# 07-FPGA.net
KiCad netlist of a schematic drawn in Altium Designer
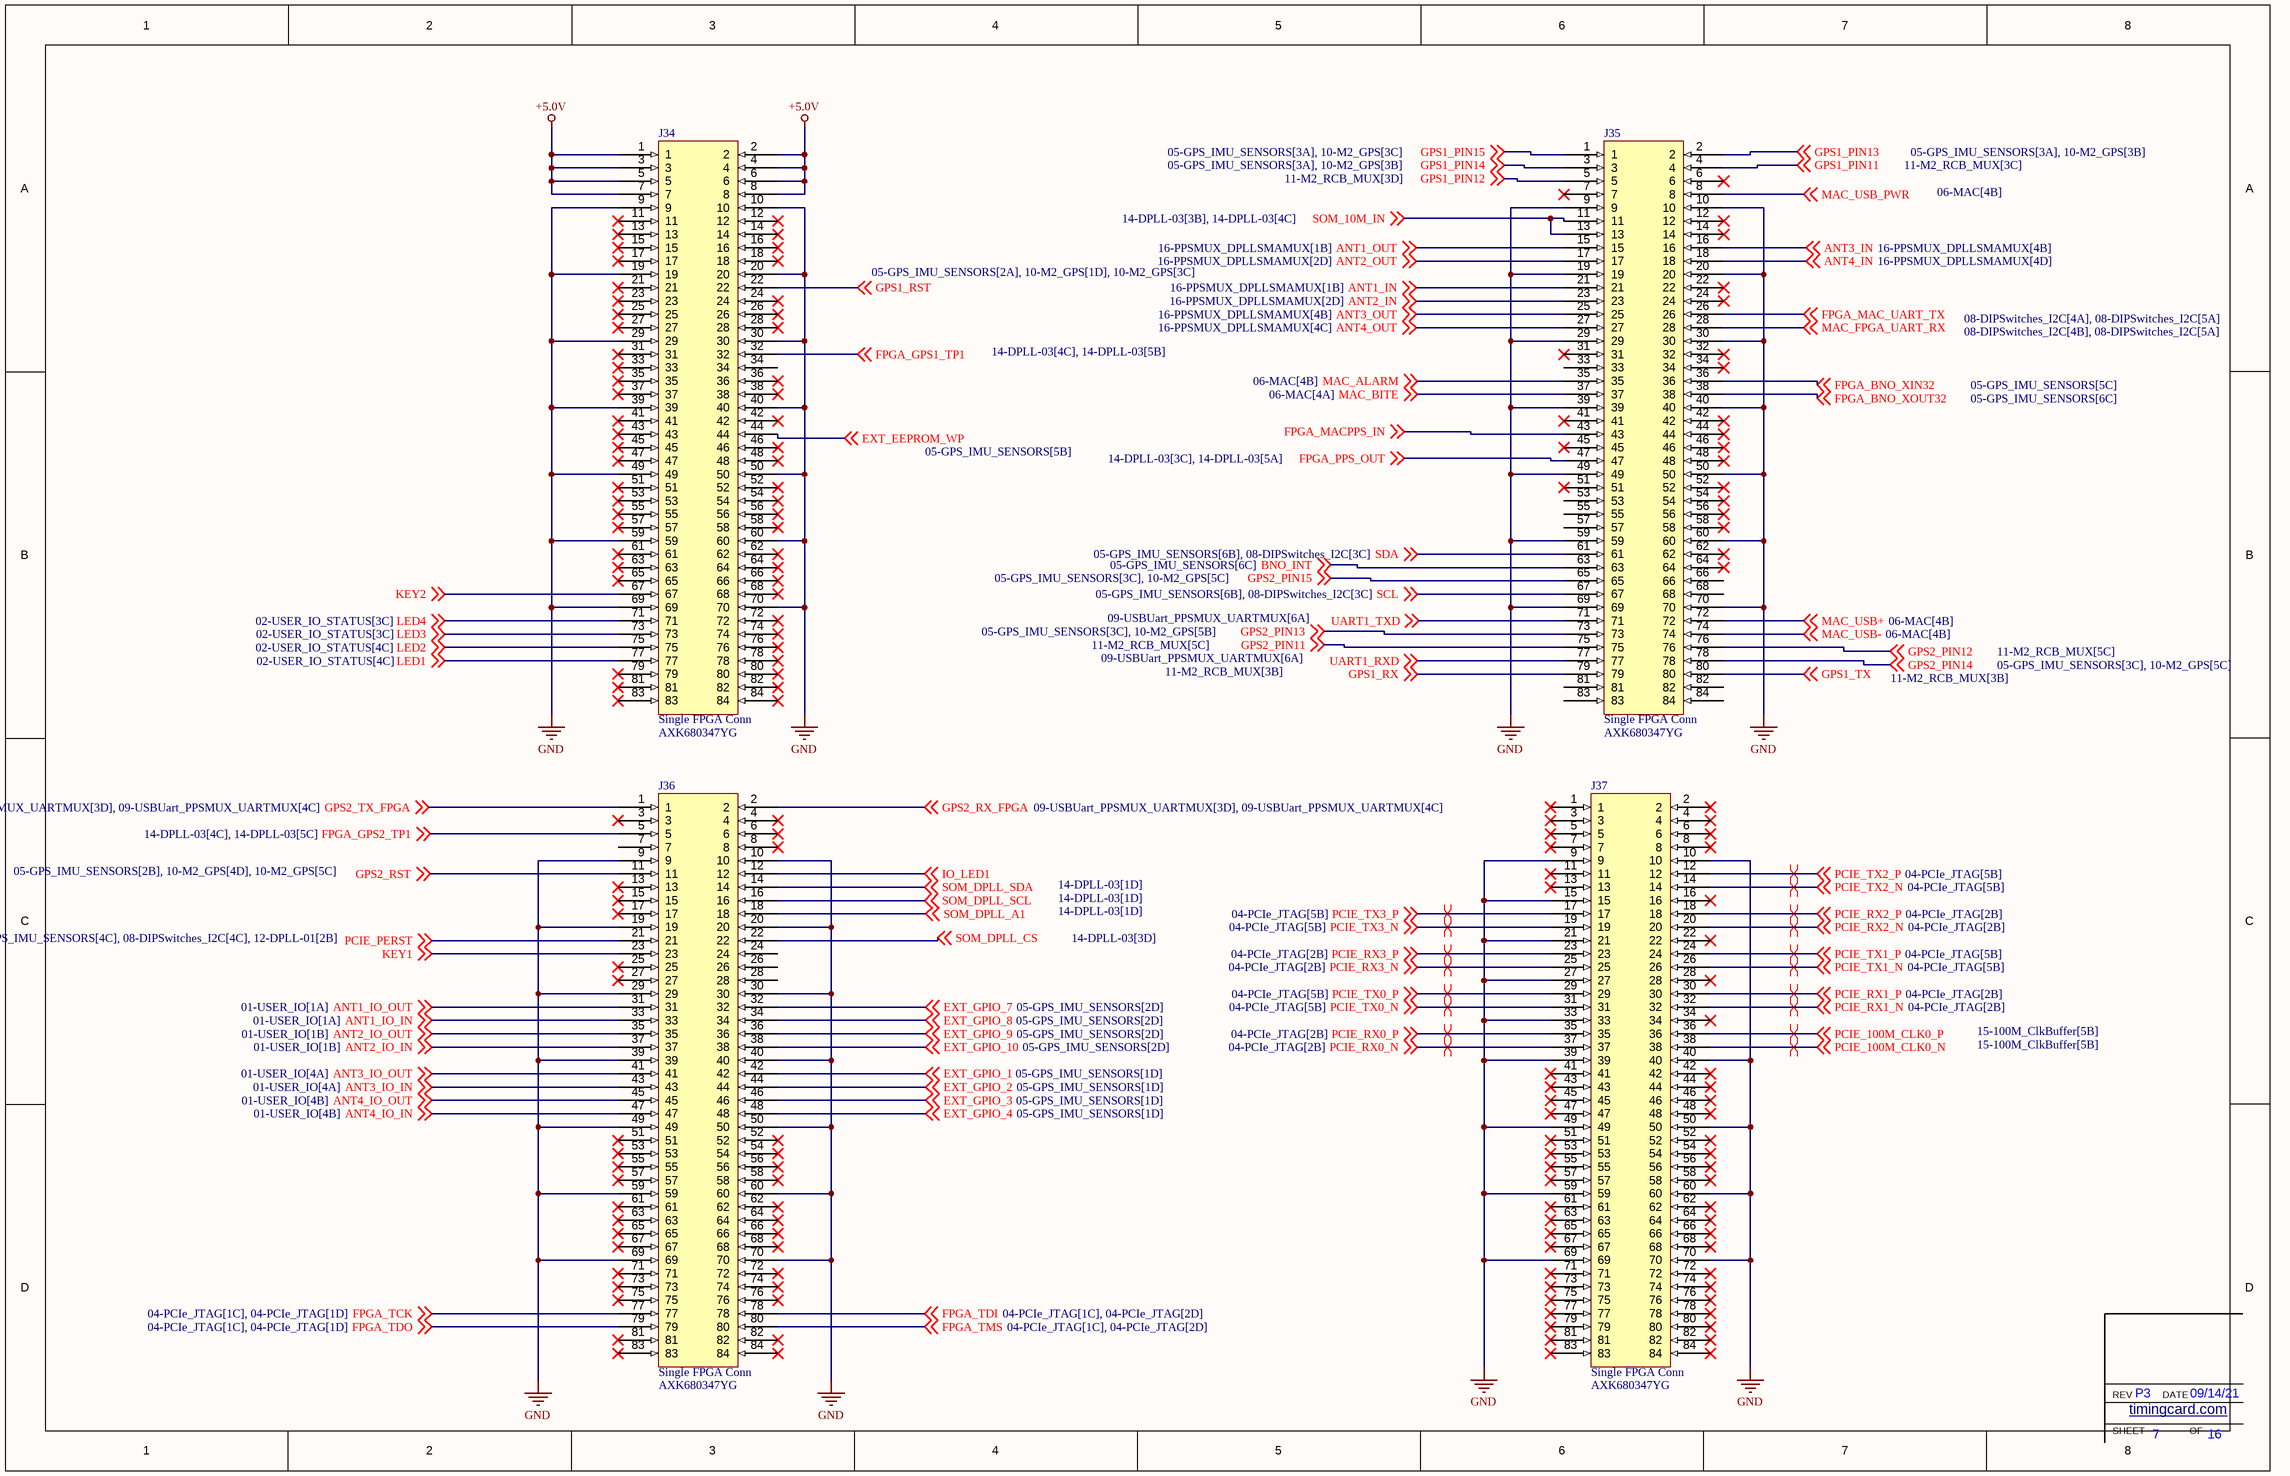
[diagram p0: 07-FPGA.SchDoc]

(export (version "E")
  (design (tool "Eeschema 10.0.6"))
  (components
    (comp (ref "J34")
      (value "Single FPGA Conn")
      (footprint "SingleFPGAConn")
      (fields (field (name "PART NUMBER") "AXK680347YG"))
      (libsource (lib "FPGA_CONN") (part "Single FPGA Conn"))
    )
    (comp (ref "J35")
      (value "Single FPGA Conn")
      (footprint "SingleFPGAConn")
      (fields (field (name "PART NUMBER") "AXK680347YG"))
      (libsource (lib "FPGA_CONN") (part "Single FPGA Conn"))
    )
    (comp (ref "J36")
      (value "Single FPGA Conn")
      (footprint "SingleFPGAConn")
      (fields (field (name "PART NUMBER") "AXK680347YG"))
      (libsource (lib "FPGA_CONN") (part "Single FPGA Conn"))
    )
    (comp (ref "J37")
      (value "Single FPGA Conn")
      (footprint "SingleFPGAConn")
      (fields (field (name "PART NUMBER") "AXK680347YG"))
      (libsource (lib "FPGA_CONN") (part "Single FPGA Conn"))
    )
  )
  (nets
    (net (code "1") (name "+5.0V") (class "Default")
      (node (ref "J34") (pin "1") (pinfunction "1_1") (pintype "input"))
      (node (ref "J34") (pin "2") (pinfunction "2_2") (pintype "input"))
      (node (ref "J34") (pin "3") (pinfunction "3_3") (pintype "input"))
      (node (ref "J34") (pin "4") (pinfunction "4_4") (pintype "input"))
      (node (ref "J34") (pin "5") (pinfunction "5_5") (pintype "input"))
      (node (ref "J34") (pin "6") (pinfunction "6_6") (pintype "input"))
      (node (ref "J34") (pin "7") (pinfunction "7_7") (pintype "input"))
      (node (ref "J34") (pin "8") (pinfunction "8_8") (pintype "input"))
    )
    (net (code "2") (name "ANT1_IN") (class "Default")
      (node (ref "J35") (pin "21") (pinfunction "21_21") (pintype "input"))
    )
    (net (code "3") (name "ANT1_IO_IN") (class "Default")
      (node (ref "J36") (pin "33") (pinfunction "33_33") (pintype "input"))
    )
    (net (code "4") (name "ANT1_IO_OUT") (class "Default")
      (node (ref "J36") (pin "31") (pinfunction "31_31") (pintype "input"))
    )
    (net (code "5") (name "ANT1_OUT") (class "Default")
      (node (ref "J35") (pin "15") (pinfunction "15_15") (pintype "input"))
    )
    (net (code "6") (name "ANT2_IN") (class "Default")
      (node (ref "J35") (pin "23") (pinfunction "23_23") (pintype "input"))
    )
    (net (code "7") (name "ANT2_IO_IN") (class "Default")
      (node (ref "J36") (pin "37") (pinfunction "37_37") (pintype "input"))
    )
    (net (code "8") (name "ANT2_IO_OUT") (class "Default")
      (node (ref "J36") (pin "35") (pinfunction "35_35") (pintype "input"))
    )
    (net (code "9") (name "ANT2_OUT") (class "Default")
      (node (ref "J35") (pin "17") (pinfunction "17_17") (pintype "input"))
    )
    (net (code "10") (name "ANT3_IN") (class "Default")
      (node (ref "J35") (pin "16") (pinfunction "16_16") (pintype "input"))
    )
    (net (code "11") (name "ANT3_IO_IN") (class "Default")
      (node (ref "J36") (pin "43") (pinfunction "43_43") (pintype "input"))
    )
    (net (code "12") (name "ANT3_IO_OUT") (class "Default")
      (node (ref "J36") (pin "41") (pinfunction "41_41") (pintype "input"))
    )
    (net (code "13") (name "ANT3_OUT") (class "Default")
      (node (ref "J35") (pin "25") (pinfunction "25_25") (pintype "input"))
    )
    (net (code "14") (name "ANT4_IN") (class "Default")
      (node (ref "J35") (pin "18") (pinfunction "18_18") (pintype "input"))
    )
    (net (code "15") (name "ANT4_IO_IN") (class "Default")
      (node (ref "J36") (pin "47") (pinfunction "47_47") (pintype "input"))
    )
    (net (code "16") (name "ANT4_IO_OUT") (class "Default")
      (node (ref "J36") (pin "45") (pinfunction "45_45") (pintype "input"))
    )
    (net (code "17") (name "ANT4_OUT") (class "Default")
      (node (ref "J35") (pin "27") (pinfunction "27_27") (pintype "input"))
    )
    (net (code "18") (name "BNO_INT") (class "Default")
      (node (ref "J35") (pin "63") (pinfunction "63_63") (pintype "input"))
    )
    (net (code "19") (name "EXT_EEPROM_WP") (class "Default")
      (node (ref "J34") (pin "44") (pinfunction "44_44") (pintype "input"))
    )
    (net (code "20") (name "EXT_GPIO_1") (class "Default")
      (node (ref "J36") (pin "42") (pinfunction "42_42") (pintype "input"))
    )
    (net (code "21") (name "EXT_GPIO_2") (class "Default")
      (node (ref "J36") (pin "44") (pinfunction "44_44") (pintype "input"))
    )
    (net (code "22") (name "EXT_GPIO_3") (class "Default")
      (node (ref "J36") (pin "46") (pinfunction "46_46") (pintype "input"))
    )
    (net (code "23") (name "EXT_GPIO_4") (class "Default")
      (node (ref "J36") (pin "48") (pinfunction "48_48") (pintype "input"))
    )
    (net (code "24") (name "EXT_GPIO_7") (class "Default")
      (node (ref "J36") (pin "32") (pinfunction "32_32") (pintype "input"))
    )
    (net (code "25") (name "EXT_GPIO_8") (class "Default")
      (node (ref "J36") (pin "34") (pinfunction "34_34") (pintype "input"))
    )
    (net (code "26") (name "EXT_GPIO_9") (class "Default")
      (node (ref "J36") (pin "36") (pinfunction "36_36") (pintype "input"))
    )
    (net (code "27") (name "EXT_GPIO_10") (class "Default")
      (node (ref "J36") (pin "38") (pinfunction "38_38") (pintype "input"))
    )
    (net (code "28") (name "FPGA_BNO_XIN32") (class "Default")
      (node (ref "J35") (pin "36") (pinfunction "36_36") (pintype "input"))
    )
    (net (code "29") (name "FPGA_BNO_XOUT32") (class "Default")
      (node (ref "J35") (pin "38") (pinfunction "38_38") (pintype "input"))
    )
    (net (code "30") (name "FPGA_GPS1_TP1") (class "Default")
      (node (ref "J34") (pin "32") (pinfunction "32_32") (pintype "input"))
    )
    (net (code "31") (name "FPGA_GPS2_TP1") (class "Default")
      (node (ref "J36") (pin "5") (pinfunction "5_5") (pintype "input"))
    )
    (net (code "32") (name "FPGA_MACPPS_IN") (class "Default")
      (node (ref "J35") (pin "43") (pinfunction "43_43") (pintype "input"))
    )
    (net (code "33") (name "FPGA_MAC_UART_TX") (class "Default")
      (node (ref "J35") (pin "26") (pinfunction "26_26") (pintype "input"))
    )
    (net (code "34") (name "FPGA_PPS_OUT") (class "Default")
      (node (ref "J35") (pin "47") (pinfunction "47_47") (pintype "input"))
    )
    (net (code "35") (name "FPGA_TCK") (class "Default")
      (node (ref "J36") (pin "77") (pinfunction "77_77") (pintype "input"))
    )
    (net (code "36") (name "FPGA_TDI") (class "Default")
      (node (ref "J36") (pin "78") (pinfunction "78_78") (pintype "input"))
    )
    (net (code "37") (name "FPGA_TDO") (class "Default")
      (node (ref "J36") (pin "79") (pinfunction "79_79") (pintype "input"))
    )
    (net (code "38") (name "FPGA_TMS") (class "Default")
      (node (ref "J36") (pin "80") (pinfunction "80_80") (pintype "input"))
    )
    (net (code "39") (name "GND") (class "Default")
      (node (ref "J34") (pin "10") (pinfunction "10_10") (pintype "input"))
      (node (ref "J34") (pin "19") (pinfunction "19_19") (pintype "input"))
      (node (ref "J34") (pin "20") (pinfunction "20_20") (pintype "input"))
      (node (ref "J34") (pin "29") (pinfunction "29_29") (pintype "input"))
      (node (ref "J34") (pin "30") (pinfunction "30_30") (pintype "input"))
      (node (ref "J34") (pin "39") (pinfunction "39_39") (pintype "input"))
      (node (ref "J34") (pin "40") (pinfunction "40_40") (pintype "input"))
      (node (ref "J34") (pin "49") (pinfunction "49_49") (pintype "input"))
      (node (ref "J34") (pin "50") (pinfunction "50_50") (pintype "input"))
      (node (ref "J34") (pin "59") (pinfunction "59_59") (pintype "input"))
      (node (ref "J34") (pin "60") (pinfunction "60_60") (pintype "input"))
      (node (ref "J34") (pin "69") (pinfunction "69_69") (pintype "input"))
      (node (ref "J34") (pin "70") (pinfunction "70_70") (pintype "input"))
      (node (ref "J34") (pin "9") (pinfunction "9_9") (pintype "input"))
      (node (ref "J35") (pin "10") (pinfunction "10_10") (pintype "input"))
      (node (ref "J35") (pin "19") (pinfunction "19_19") (pintype "input"))
      (node (ref "J35") (pin "20") (pinfunction "20_20") (pintype "input"))
      (node (ref "J35") (pin "29") (pinfunction "29_29") (pintype "input"))
      (node (ref "J35") (pin "30") (pinfunction "30_30") (pintype "input"))
      (node (ref "J35") (pin "39") (pinfunction "39_39") (pintype "input"))
      (node (ref "J35") (pin "40") (pinfunction "40_40") (pintype "input"))
      (node (ref "J35") (pin "49") (pinfunction "49_49") (pintype "input"))
      (node (ref "J35") (pin "50") (pinfunction "50_50") (pintype "input"))
      (node (ref "J35") (pin "59") (pinfunction "59_59") (pintype "input"))
      (node (ref "J35") (pin "60") (pinfunction "60_60") (pintype "input"))
      (node (ref "J35") (pin "69") (pinfunction "69_69") (pintype "input"))
      (node (ref "J35") (pin "70") (pinfunction "70_70") (pintype "input"))
      (node (ref "J35") (pin "9") (pinfunction "9_9") (pintype "input"))
      (node (ref "J36") (pin "10") (pinfunction "10_10") (pintype "input"))
      (node (ref "J36") (pin "19") (pinfunction "19_19") (pintype "input"))
      (node (ref "J36") (pin "20") (pinfunction "20_20") (pintype "input"))
      (node (ref "J36") (pin "29") (pinfunction "29_29") (pintype "input"))
      (node (ref "J36") (pin "30") (pinfunction "30_30") (pintype "input"))
      (node (ref "J36") (pin "39") (pinfunction "39_39") (pintype "input"))
      (node (ref "J36") (pin "40") (pinfunction "40_40") (pintype "input"))
      (node (ref "J36") (pin "49") (pinfunction "49_49") (pintype "input"))
      (node (ref "J36") (pin "50") (pinfunction "50_50") (pintype "input"))
      (node (ref "J36") (pin "59") (pinfunction "59_59") (pintype "input"))
      (node (ref "J36") (pin "60") (pinfunction "60_60") (pintype "input"))
      (node (ref "J36") (pin "69") (pinfunction "69_69") (pintype "input"))
      (node (ref "J36") (pin "70") (pinfunction "70_70") (pintype "input"))
      (node (ref "J36") (pin "9") (pinfunction "9_9") (pintype "input"))
      (node (ref "J37") (pin "10") (pinfunction "10_10") (pintype "input"))
      (node (ref "J37") (pin "15") (pinfunction "15_15") (pintype "input"))
      (node (ref "J37") (pin "21") (pinfunction "21_21") (pintype "input"))
      (node (ref "J37") (pin "27") (pinfunction "27_27") (pintype "input"))
      (node (ref "J37") (pin "33") (pinfunction "33_33") (pintype "input"))
      (node (ref "J37") (pin "39") (pinfunction "39_39") (pintype "input"))
      (node (ref "J37") (pin "40") (pinfunction "40_40") (pintype "input"))
      (node (ref "J37") (pin "49") (pinfunction "49_49") (pintype "input"))
      (node (ref "J37") (pin "50") (pinfunction "50_50") (pintype "input"))
      (node (ref "J37") (pin "59") (pinfunction "59_59") (pintype "input"))
      (node (ref "J37") (pin "60") (pinfunction "60_60") (pintype "input"))
      (node (ref "J37") (pin "69") (pinfunction "69_69") (pintype "input"))
      (node (ref "J37") (pin "70") (pinfunction "70_70") (pintype "input"))
      (node (ref "J37") (pin "9") (pinfunction "9_9") (pintype "input"))
    )
    (net (code "40") (name "GPS1_PIN11") (class "Default")
      (node (ref "J35") (pin "4") (pinfunction "4_4") (pintype "input"))
    )
    (net (code "41") (name "GPS1_PIN12") (class "Default")
      (node (ref "J35") (pin "5") (pinfunction "5_5") (pintype "input"))
    )
    (net (code "42") (name "GPS1_PIN13") (class "Default")
      (node (ref "J35") (pin "2") (pinfunction "2_2") (pintype "input"))
    )
    (net (code "43") (name "GPS1_PIN14") (class "Default")
      (node (ref "J35") (pin "3") (pinfunction "3_3") (pintype "input"))
    )
    (net (code "44") (name "GPS1_PIN15") (class "Default")
      (node (ref "J35") (pin "1") (pinfunction "1_1") (pintype "input"))
    )
    (net (code "45") (name "GPS1_RST") (class "Default")
      (node (ref "J34") (pin "22") (pinfunction "22_22") (pintype "input"))
    )
    (net (code "46") (name "GPS1_RX") (class "Default")
      (node (ref "J35") (pin "79") (pinfunction "79_79") (pintype "input"))
    )
    (net (code "47") (name "GPS1_TX") (class "Default")
      (node (ref "J35") (pin "80") (pinfunction "80_80") (pintype "input"))
    )
    (net (code "48") (name "GPS2_PIN11") (class "Default")
      (node (ref "J35") (pin "75") (pinfunction "75_75") (pintype "input"))
    )
    (net (code "49") (name "GPS2_PIN12") (class "Default")
      (node (ref "J35") (pin "76") (pinfunction "76_76") (pintype "input"))
    )
    (net (code "50") (name "GPS2_PIN13") (class "Default")
      (node (ref "J35") (pin "73") (pinfunction "73_73") (pintype "input"))
    )
    (net (code "51") (name "GPS2_PIN14") (class "Default")
      (node (ref "J35") (pin "78") (pinfunction "78_78") (pintype "input"))
    )
    (net (code "52") (name "GPS2_PIN15") (class "Default")
      (node (ref "J35") (pin "65") (pinfunction "65_65") (pintype "input"))
    )
    (net (code "53") (name "GPS2_RST") (class "Default")
      (node (ref "J36") (pin "11") (pinfunction "11_11") (pintype "input"))
    )
    (net (code "54") (name "GPS2_RX_FPGA") (class "Default")
      (node (ref "J36") (pin "2") (pinfunction "2_2") (pintype "input"))
    )
    (net (code "55") (name "GPS2_TX_FPGA") (class "Default")
      (node (ref "J36") (pin "1") (pinfunction "1_1") (pintype "input"))
    )
    (net (code "56") (name "IO_LED1") (class "Default")
      (node (ref "J36") (pin "12") (pinfunction "12_12") (pintype "input"))
    )
    (net (code "57") (name "KEY1") (class "Default")
      (node (ref "J36") (pin "23") (pinfunction "23_23") (pintype "input"))
    )
    (net (code "58") (name "KEY2") (class "Default")
      (node (ref "J34") (pin "67") (pinfunction "67_67") (pintype "input"))
    )
    (net (code "59") (name "LED1") (class "Default")
      (node (ref "J34") (pin "77") (pinfunction "77_77") (pintype "input"))
    )
    (net (code "60") (name "LED2") (class "Default")
      (node (ref "J34") (pin "75") (pinfunction "75_75") (pintype "input"))
    )
    (net (code "61") (name "LED3") (class "Default")
      (node (ref "J34") (pin "73") (pinfunction "73_73") (pintype "input"))
    )
    (net (code "62") (name "LED4") (class "Default")
      (node (ref "J34") (pin "71") (pinfunction "71_71") (pintype "input"))
    )
    (net (code "63") (name "MAC_ALARM") (class "Default")
      (node (ref "J35") (pin "35") (pinfunction "35_35") (pintype "input"))
    )
    (net (code "64") (name "MAC_BITE") (class "Default")
      (node (ref "J35") (pin "37") (pinfunction "37_37") (pintype "input"))
    )
    (net (code "65") (name "MAC_FPGA_UART_RX") (class "Default")
      (node (ref "J35") (pin "28") (pinfunction "28_28") (pintype "input"))
    )
    (net (code "66") (name "MAC_USB+") (class "Default")
      (node (ref "J35") (pin "72") (pinfunction "72_72") (pintype "input"))
    )
    (net (code "67") (name "MAC_USB-") (class "Default")
      (node (ref "J35") (pin "74") (pinfunction "74_74") (pintype "input"))
    )
    (net (code "68") (name "MAC_USB_PWR") (class "Default")
      (node (ref "J35") (pin "8") (pinfunction "8_8") (pintype "input"))
    )
    (net (code "69") (name "PCIE_100M_CLK0_N") (class "Default")
      (node (ref "J37") (pin "38") (pinfunction "38_38") (pintype "input"))
    )
    (net (code "70") (name "PCIE_100M_CLK0_P") (class "Default")
      (node (ref "J37") (pin "36") (pinfunction "36_36") (pintype "input"))
    )
    (net (code "71") (name "PCIE_PERST") (class "Default")
      (node (ref "J36") (pin "21") (pinfunction "21_21") (pintype "input"))
    )
    (net (code "72") (name "PCIE_RX0_N") (class "Default")
      (node (ref "J37") (pin "37") (pinfunction "37_37") (pintype "input"))
    )
    (net (code "73") (name "PCIE_RX0_P") (class "Default")
      (node (ref "J37") (pin "35") (pinfunction "35_35") (pintype "input"))
    )
    (net (code "74") (name "PCIE_RX1_N") (class "Default")
      (node (ref "J37") (pin "32") (pinfunction "32_32") (pintype "input"))
    )
    (net (code "75") (name "PCIE_RX1_P") (class "Default")
      (node (ref "J37") (pin "30") (pinfunction "30_30") (pintype "input"))
    )
    (net (code "76") (name "PCIE_RX2_N") (class "Default")
      (node (ref "J37") (pin "20") (pinfunction "20_20") (pintype "input"))
    )
    (net (code "77") (name "PCIE_RX2_P") (class "Default")
      (node (ref "J37") (pin "18") (pinfunction "18_18") (pintype "input"))
    )
    (net (code "78") (name "PCIE_RX3_N") (class "Default")
      (node (ref "J37") (pin "25") (pinfunction "25_25") (pintype "input"))
    )
    (net (code "79") (name "PCIE_RX3_P") (class "Default")
      (node (ref "J37") (pin "23") (pinfunction "23_23") (pintype "input"))
    )
    (net (code "80") (name "PCIE_TX0_N") (class "Default")
      (node (ref "J37") (pin "31") (pinfunction "31_31") (pintype "input"))
    )
    (net (code "81") (name "PCIE_TX0_P") (class "Default")
      (node (ref "J37") (pin "29") (pinfunction "29_29") (pintype "input"))
    )
    (net (code "82") (name "PCIE_TX1_N") (class "Default")
      (node (ref "J37") (pin "26") (pinfunction "26_26") (pintype "input"))
    )
    (net (code "83") (name "PCIE_TX1_P") (class "Default")
      (node (ref "J37") (pin "24") (pinfunction "24_24") (pintype "input"))
    )
    (net (code "84") (name "PCIE_TX2_N") (class "Default")
      (node (ref "J37") (pin "14") (pinfunction "14_14") (pintype "input"))
    )
    (net (code "85") (name "PCIE_TX2_P") (class "Default")
      (node (ref "J37") (pin "12") (pinfunction "12_12") (pintype "input"))
    )
    (net (code "86") (name "PCIE_TX3_N") (class "Default")
      (node (ref "J37") (pin "19") (pinfunction "19_19") (pintype "input"))
    )
    (net (code "87") (name "PCIE_TX3_P") (class "Default")
      (node (ref "J37") (pin "17") (pinfunction "17_17") (pintype "input"))
    )
    (net (code "88") (name "SCL") (class "Default")
      (node (ref "J35") (pin "67") (pinfunction "67_67") (pintype "input"))
    )
    (net (code "89") (name "SDA") (class "Default")
      (node (ref "J35") (pin "61") (pinfunction "61_61") (pintype "input"))
    )
    (net (code "90") (name "SOM_10M_IN") (class "Default")
      (node (ref "J35") (pin "11") (pinfunction "11_11") (pintype "input"))
      (node (ref "J35") (pin "13") (pinfunction "13_13") (pintype "input"))
    )
    (net (code "91") (name "SOM_DPLL_A1") (class "Default")
      (node (ref "J36") (pin "18") (pinfunction "18_18") (pintype "input"))
    )
    (net (code "92") (name "SOM_DPLL_CS") (class "Default")
      (node (ref "J36") (pin "22") (pinfunction "22_22") (pintype "input"))
    )
    (net (code "93") (name "SOM_DPLL_SCL") (class "Default")
      (node (ref "J36") (pin "16") (pinfunction "16_16") (pintype "input"))
    )
    (net (code "94") (name "SOM_DPLL_SDA") (class "Default")
      (node (ref "J36") (pin "14") (pinfunction "14_14") (pintype "input"))
    )
    (net (code "95") (name "UART1_RXD") (class "Default")
      (node (ref "J35") (pin "77") (pinfunction "77_77") (pintype "input"))
    )
    (net (code "96") (name "UART1_TXD") (class "Default")
      (node (ref "J35") (pin "71") (pinfunction "71_71") (pintype "input"))
    )
    (net (code "97") (name "unconnected-(J34-Pad11)") (class "Default")
      (node (ref "J34") (pin "11") (pinfunction "11_11") (pintype "input+no_connect"))
    )
    (net (code "98") (name "unconnected-(J34-Pad12)") (class "Default")
      (node (ref "J34") (pin "12") (pinfunction "12_12") (pintype "input+no_connect"))
    )
    (net (code "99") (name "unconnected-(J34-Pad13)") (class "Default")
      (node (ref "J34") (pin "13") (pinfunction "13_13") (pintype "input+no_connect"))
    )
    (net (code "100") (name "unconnected-(J34-Pad14)") (class "Default")
      (node (ref "J34") (pin "14") (pinfunction "14_14") (pintype "input+no_connect"))
    )
    (net (code "101") (name "unconnected-(J34-Pad15)") (class "Default")
      (node (ref "J34") (pin "15") (pinfunction "15_15") (pintype "input+no_connect"))
    )
    (net (code "102") (name "unconnected-(J34-Pad16)") (class "Default")
      (node (ref "J34") (pin "16") (pinfunction "16_16") (pintype "input+no_connect"))
    )
    (net (code "103") (name "unconnected-(J34-Pad17)") (class "Default")
      (node (ref "J34") (pin "17") (pinfunction "17_17") (pintype "input+no_connect"))
    )
    (net (code "104") (name "unconnected-(J34-Pad18)") (class "Default")
      (node (ref "J34") (pin "18") (pinfunction "18_18") (pintype "input+no_connect"))
    )
    (net (code "105") (name "unconnected-(J34-Pad21)") (class "Default")
      (node (ref "J34") (pin "21") (pinfunction "21_21") (pintype "input+no_connect"))
    )
    (net (code "106") (name "unconnected-(J34-Pad23)") (class "Default")
      (node (ref "J34") (pin "23") (pinfunction "23_23") (pintype "input+no_connect"))
    )
    (net (code "107") (name "unconnected-(J34-Pad24)") (class "Default")
      (node (ref "J34") (pin "24") (pinfunction "24_24") (pintype "input+no_connect"))
    )
    (net (code "108") (name "unconnected-(J34-Pad25)") (class "Default")
      (node (ref "J34") (pin "25") (pinfunction "25_25") (pintype "input+no_connect"))
    )
    (net (code "109") (name "unconnected-(J34-Pad26)") (class "Default")
      (node (ref "J34") (pin "26") (pinfunction "26_26") (pintype "input+no_connect"))
    )
    (net (code "110") (name "unconnected-(J34-Pad27)") (class "Default")
      (node (ref "J34") (pin "27") (pinfunction "27_27") (pintype "input+no_connect"))
    )
    (net (code "111") (name "unconnected-(J34-Pad28)") (class "Default")
      (node (ref "J34") (pin "28") (pinfunction "28_28") (pintype "input+no_connect"))
    )
    (net (code "112") (name "unconnected-(J34-Pad31)") (class "Default")
      (node (ref "J34") (pin "31") (pinfunction "31_31") (pintype "input+no_connect"))
    )
    (net (code "113") (name "unconnected-(J34-Pad33)") (class "Default")
      (node (ref "J34") (pin "33") (pinfunction "33_33") (pintype "input+no_connect"))
    )
    (net (code "114") (name "unconnected-(J34-Pad34)") (class "Default")
      (node (ref "J34") (pin "34") (pinfunction "34_34") (pintype "input"))
    )
    (net (code "115") (name "unconnected-(J34-Pad35)") (class "Default")
      (node (ref "J34") (pin "35") (pinfunction "35_35") (pintype "input+no_connect"))
    )
    (net (code "116") (name "unconnected-(J34-Pad36)") (class "Default")
      (node (ref "J34") (pin "36") (pinfunction "36_36") (pintype "input+no_connect"))
    )
    (net (code "117") (name "unconnected-(J34-Pad37)") (class "Default")
      (node (ref "J34") (pin "37") (pinfunction "37_37") (pintype "input+no_connect"))
    )
    (net (code "118") (name "unconnected-(J34-Pad38)") (class "Default")
      (node (ref "J34") (pin "38") (pinfunction "38_38") (pintype "input+no_connect"))
    )
    (net (code "119") (name "unconnected-(J34-Pad41)") (class "Default")
      (node (ref "J34") (pin "41") (pinfunction "41_41") (pintype "input+no_connect"))
    )
    (net (code "120") (name "unconnected-(J34-Pad42)") (class "Default")
      (node (ref "J34") (pin "42") (pinfunction "42_42") (pintype "input+no_connect"))
    )
    (net (code "121") (name "unconnected-(J34-Pad43)") (class "Default")
      (node (ref "J34") (pin "43") (pinfunction "43_43") (pintype "input+no_connect"))
    )
    (net (code "122") (name "unconnected-(J34-Pad45)") (class "Default")
      (node (ref "J34") (pin "45") (pinfunction "45_45") (pintype "input+no_connect"))
    )
    (net (code "123") (name "unconnected-(J34-Pad46)") (class "Default")
      (node (ref "J34") (pin "46") (pinfunction "46_46") (pintype "input+no_connect"))
    )
    (net (code "124") (name "unconnected-(J34-Pad47)") (class "Default")
      (node (ref "J34") (pin "47") (pinfunction "47_47") (pintype "input+no_connect"))
    )
    (net (code "125") (name "unconnected-(J34-Pad48)") (class "Default")
      (node (ref "J34") (pin "48") (pinfunction "48_48") (pintype "input+no_connect"))
    )
    (net (code "126") (name "unconnected-(J34-Pad51)") (class "Default")
      (node (ref "J34") (pin "51") (pinfunction "51_51") (pintype "input+no_connect"))
    )
    (net (code "127") (name "unconnected-(J34-Pad52)") (class "Default")
      (node (ref "J34") (pin "52") (pinfunction "52_52") (pintype "input+no_connect"))
    )
    (net (code "128") (name "unconnected-(J34-Pad53)") (class "Default")
      (node (ref "J34") (pin "53") (pinfunction "53_53") (pintype "input+no_connect"))
    )
    (net (code "129") (name "unconnected-(J34-Pad54)") (class "Default")
      (node (ref "J34") (pin "54") (pinfunction "54_54") (pintype "input+no_connect"))
    )
    (net (code "130") (name "unconnected-(J34-Pad55)") (class "Default")
      (node (ref "J34") (pin "55") (pinfunction "55_55") (pintype "input+no_connect"))
    )
    (net (code "131") (name "unconnected-(J34-Pad56)") (class "Default")
      (node (ref "J34") (pin "56") (pinfunction "56_56") (pintype "input+no_connect"))
    )
    (net (code "132") (name "unconnected-(J34-Pad57)") (class "Default")
      (node (ref "J34") (pin "57") (pinfunction "57_57") (pintype "input+no_connect"))
    )
    (net (code "133") (name "unconnected-(J34-Pad58)") (class "Default")
      (node (ref "J34") (pin "58") (pinfunction "58_58") (pintype "input+no_connect"))
    )
    (net (code "134") (name "unconnected-(J34-Pad61)") (class "Default")
      (node (ref "J34") (pin "61") (pinfunction "61_61") (pintype "input+no_connect"))
    )
    (net (code "135") (name "unconnected-(J34-Pad62)") (class "Default")
      (node (ref "J34") (pin "62") (pinfunction "62_62") (pintype "input+no_connect"))
    )
    (net (code "136") (name "unconnected-(J34-Pad63)") (class "Default")
      (node (ref "J34") (pin "63") (pinfunction "63_63") (pintype "input+no_connect"))
    )
    (net (code "137") (name "unconnected-(J34-Pad64)") (class "Default")
      (node (ref "J34") (pin "64") (pinfunction "64_64") (pintype "input+no_connect"))
    )
    (net (code "138") (name "unconnected-(J34-Pad65)") (class "Default")
      (node (ref "J34") (pin "65") (pinfunction "65_65") (pintype "input+no_connect"))
    )
    (net (code "139") (name "unconnected-(J34-Pad66)") (class "Default")
      (node (ref "J34") (pin "66") (pinfunction "66_66") (pintype "input+no_connect"))
    )
    (net (code "140") (name "unconnected-(J34-Pad68)") (class "Default")
      (node (ref "J34") (pin "68") (pinfunction "68_68") (pintype "input+no_connect"))
    )
    (net (code "141") (name "unconnected-(J34-Pad72)") (class "Default")
      (node (ref "J34") (pin "72") (pinfunction "72_72") (pintype "input+no_connect"))
    )
    (net (code "142") (name "unconnected-(J34-Pad74)") (class "Default")
      (node (ref "J34") (pin "74") (pinfunction "74_74") (pintype "input+no_connect"))
    )
    (net (code "143") (name "unconnected-(J34-Pad76)") (class "Default")
      (node (ref "J34") (pin "76") (pinfunction "76_76") (pintype "input+no_connect"))
    )
    (net (code "144") (name "unconnected-(J34-Pad78)") (class "Default")
      (node (ref "J34") (pin "78") (pinfunction "78_78") (pintype "input+no_connect"))
    )
    (net (code "145") (name "unconnected-(J34-Pad79)") (class "Default")
      (node (ref "J34") (pin "79") (pinfunction "79_79") (pintype "input+no_connect"))
    )
    (net (code "146") (name "unconnected-(J34-Pad80)") (class "Default")
      (node (ref "J34") (pin "80") (pinfunction "80_80") (pintype "input+no_connect"))
    )
    (net (code "147") (name "unconnected-(J34-Pad81)") (class "Default")
      (node (ref "J34") (pin "81") (pinfunction "81_81") (pintype "input+no_connect"))
    )
    (net (code "148") (name "unconnected-(J34-Pad82)") (class "Default")
      (node (ref "J34") (pin "82") (pinfunction "82_82") (pintype "input+no_connect"))
    )
    (net (code "149") (name "unconnected-(J34-Pad83)") (class "Default")
      (node (ref "J34") (pin "83") (pinfunction "83_83") (pintype "input+no_connect"))
    )
    (net (code "150") (name "unconnected-(J34-Pad84)") (class "Default")
      (node (ref "J34") (pin "84") (pinfunction "84_84") (pintype "input+no_connect"))
    )
    (net (code "151") (name "unconnected-(J35-Pad6)") (class "Default")
      (node (ref "J35") (pin "6") (pinfunction "6_6") (pintype "input+no_connect"))
    )
    (net (code "152") (name "unconnected-(J35-Pad7)") (class "Default")
      (node (ref "J35") (pin "7") (pinfunction "7_7") (pintype "input+no_connect"))
    )
    (net (code "153") (name "unconnected-(J35-Pad12)") (class "Default")
      (node (ref "J35") (pin "12") (pinfunction "12_12") (pintype "input+no_connect"))
    )
    (net (code "154") (name "unconnected-(J35-Pad14)") (class "Default")
      (node (ref "J35") (pin "14") (pinfunction "14_14") (pintype "input+no_connect"))
    )
    (net (code "155") (name "unconnected-(J35-Pad22)") (class "Default")
      (node (ref "J35") (pin "22") (pinfunction "22_22") (pintype "input+no_connect"))
    )
    (net (code "156") (name "unconnected-(J35-Pad24)") (class "Default")
      (node (ref "J35") (pin "24") (pinfunction "24_24") (pintype "input+no_connect"))
    )
    (net (code "157") (name "unconnected-(J35-Pad31)") (class "Default")
      (node (ref "J35") (pin "31") (pinfunction "31_31") (pintype "input+no_connect"))
    )
    (net (code "158") (name "unconnected-(J35-Pad32)") (class "Default")
      (node (ref "J35") (pin "32") (pinfunction "32_32") (pintype "input+no_connect"))
    )
    (net (code "159") (name "unconnected-(J35-Pad33)") (class "Default")
      (node (ref "J35") (pin "33") (pinfunction "33_33") (pintype "input"))
    )
    (net (code "160") (name "unconnected-(J35-Pad34)") (class "Default")
      (node (ref "J35") (pin "34") (pinfunction "34_34") (pintype "input+no_connect"))
    )
    (net (code "161") (name "unconnected-(J35-Pad41)") (class "Default")
      (node (ref "J35") (pin "41") (pinfunction "41_41") (pintype "input+no_connect"))
    )
    (net (code "162") (name "unconnected-(J35-Pad42)") (class "Default")
      (node (ref "J35") (pin "42") (pinfunction "42_42") (pintype "input+no_connect"))
    )
    (net (code "163") (name "unconnected-(J35-Pad44)") (class "Default")
      (node (ref "J35") (pin "44") (pinfunction "44_44") (pintype "input+no_connect"))
    )
    (net (code "164") (name "unconnected-(J35-Pad45)") (class "Default")
      (node (ref "J35") (pin "45") (pinfunction "45_45") (pintype "input+no_connect"))
    )
    (net (code "165") (name "unconnected-(J35-Pad46)") (class "Default")
      (node (ref "J35") (pin "46") (pinfunction "46_46") (pintype "input+no_connect"))
    )
    (net (code "166") (name "unconnected-(J35-Pad48)") (class "Default")
      (node (ref "J35") (pin "48") (pinfunction "48_48") (pintype "input+no_connect"))
    )
    (net (code "167") (name "unconnected-(J35-Pad51)") (class "Default")
      (node (ref "J35") (pin "51") (pinfunction "51_51") (pintype "input+no_connect"))
    )
    (net (code "168") (name "unconnected-(J35-Pad52)") (class "Default")
      (node (ref "J35") (pin "52") (pinfunction "52_52") (pintype "input+no_connect"))
    )
    (net (code "169") (name "unconnected-(J35-Pad53)") (class "Default")
      (node (ref "J35") (pin "53") (pinfunction "53_53") (pintype "input"))
    )
    (net (code "170") (name "unconnected-(J35-Pad54)") (class "Default")
      (node (ref "J35") (pin "54") (pinfunction "54_54") (pintype "input+no_connect"))
    )
    (net (code "171") (name "unconnected-(J35-Pad55)") (class "Default")
      (node (ref "J35") (pin "55") (pinfunction "55_55") (pintype "input"))
    )
    (net (code "172") (name "unconnected-(J35-Pad56)") (class "Default")
      (node (ref "J35") (pin "56") (pinfunction "56_56") (pintype "input+no_connect"))
    )
    (net (code "173") (name "unconnected-(J35-Pad57)") (class "Default")
      (node (ref "J35") (pin "57") (pinfunction "57_57") (pintype "input"))
    )
    (net (code "174") (name "unconnected-(J35-Pad58)") (class "Default")
      (node (ref "J35") (pin "58") (pinfunction "58_58") (pintype "input+no_connect"))
    )
    (net (code "175") (name "unconnected-(J35-Pad62)") (class "Default")
      (node (ref "J35") (pin "62") (pinfunction "62_62") (pintype "input+no_connect"))
    )
    (net (code "176") (name "unconnected-(J35-Pad64)") (class "Default")
      (node (ref "J35") (pin "64") (pinfunction "64_64") (pintype "input+no_connect"))
    )
    (net (code "177") (name "unconnected-(J35-Pad66)") (class "Default")
      (node (ref "J35") (pin "66") (pinfunction "66_66") (pintype "input"))
    )
    (net (code "178") (name "unconnected-(J35-Pad68)") (class "Default")
      (node (ref "J35") (pin "68") (pinfunction "68_68") (pintype "input"))
    )
    (net (code "179") (name "unconnected-(J35-Pad81)") (class "Default")
      (node (ref "J35") (pin "81") (pinfunction "81_81") (pintype "input"))
    )
    (net (code "180") (name "unconnected-(J35-Pad82)") (class "Default")
      (node (ref "J35") (pin "82") (pinfunction "82_82") (pintype "input"))
    )
    (net (code "181") (name "unconnected-(J35-Pad83)") (class "Default")
      (node (ref "J35") (pin "83") (pinfunction "83_83") (pintype "input"))
    )
    (net (code "182") (name "unconnected-(J35-Pad84)") (class "Default")
      (node (ref "J35") (pin "84") (pinfunction "84_84") (pintype "input"))
    )
    (net (code "183") (name "unconnected-(J36-Pad3)") (class "Default")
      (node (ref "J36") (pin "3") (pinfunction "3_3") (pintype "input+no_connect"))
    )
    (net (code "184") (name "unconnected-(J36-Pad4)") (class "Default")
      (node (ref "J36") (pin "4") (pinfunction "4_4") (pintype "input+no_connect"))
    )
    (net (code "185") (name "unconnected-(J36-Pad6)") (class "Default")
      (node (ref "J36") (pin "6") (pinfunction "6_6") (pintype "input+no_connect"))
    )
    (net (code "186") (name "unconnected-(J36-Pad7)") (class "Default")
      (node (ref "J36") (pin "7") (pinfunction "7_7") (pintype "input"))
    )
    (net (code "187") (name "unconnected-(J36-Pad8)") (class "Default")
      (node (ref "J36") (pin "8") (pinfunction "8_8") (pintype "input+no_connect"))
    )
    (net (code "188") (name "unconnected-(J36-Pad13)") (class "Default")
      (node (ref "J36") (pin "13") (pinfunction "13_13") (pintype "input+no_connect"))
    )
    (net (code "189") (name "unconnected-(J36-Pad15)") (class "Default")
      (node (ref "J36") (pin "15") (pinfunction "15_15") (pintype "input+no_connect"))
    )
    (net (code "190") (name "unconnected-(J36-Pad17)") (class "Default")
      (node (ref "J36") (pin "17") (pinfunction "17_17") (pintype "input+no_connect"))
    )
    (net (code "191") (name "unconnected-(J36-Pad24)") (class "Default")
      (node (ref "J36") (pin "24") (pinfunction "24_24") (pintype "input"))
    )
    (net (code "192") (name "unconnected-(J36-Pad25)") (class "Default")
      (node (ref "J36") (pin "25") (pinfunction "25_25") (pintype "input+no_connect"))
    )
    (net (code "193") (name "unconnected-(J36-Pad26)") (class "Default")
      (node (ref "J36") (pin "26") (pinfunction "26_26") (pintype "input"))
    )
    (net (code "194") (name "unconnected-(J36-Pad27)") (class "Default")
      (node (ref "J36") (pin "27") (pinfunction "27_27") (pintype "input+no_connect"))
    )
    (net (code "195") (name "unconnected-(J36-Pad28)") (class "Default")
      (node (ref "J36") (pin "28") (pinfunction "28_28") (pintype "input"))
    )
    (net (code "196") (name "unconnected-(J36-Pad51)") (class "Default")
      (node (ref "J36") (pin "51") (pinfunction "51_51") (pintype "input+no_connect"))
    )
    (net (code "197") (name "unconnected-(J36-Pad52)") (class "Default")
      (node (ref "J36") (pin "52") (pinfunction "52_52") (pintype "input+no_connect"))
    )
    (net (code "198") (name "unconnected-(J36-Pad53)") (class "Default")
      (node (ref "J36") (pin "53") (pinfunction "53_53") (pintype "input+no_connect"))
    )
    (net (code "199") (name "unconnected-(J36-Pad54)") (class "Default")
      (node (ref "J36") (pin "54") (pinfunction "54_54") (pintype "input+no_connect"))
    )
    (net (code "200") (name "unconnected-(J36-Pad55)") (class "Default")
      (node (ref "J36") (pin "55") (pinfunction "55_55") (pintype "input+no_connect"))
    )
    (net (code "201") (name "unconnected-(J36-Pad56)") (class "Default")
      (node (ref "J36") (pin "56") (pinfunction "56_56") (pintype "input+no_connect"))
    )
    (net (code "202") (name "unconnected-(J36-Pad57)") (class "Default")
      (node (ref "J36") (pin "57") (pinfunction "57_57") (pintype "input+no_connect"))
    )
    (net (code "203") (name "unconnected-(J36-Pad58)") (class "Default")
      (node (ref "J36") (pin "58") (pinfunction "58_58") (pintype "input+no_connect"))
    )
    (net (code "204") (name "unconnected-(J36-Pad61)") (class "Default")
      (node (ref "J36") (pin "61") (pinfunction "61_61") (pintype "input+no_connect"))
    )
    (net (code "205") (name "unconnected-(J36-Pad62)") (class "Default")
      (node (ref "J36") (pin "62") (pinfunction "62_62") (pintype "input+no_connect"))
    )
    (net (code "206") (name "unconnected-(J36-Pad63)") (class "Default")
      (node (ref "J36") (pin "63") (pinfunction "63_63") (pintype "input+no_connect"))
    )
    (net (code "207") (name "unconnected-(J36-Pad64)") (class "Default")
      (node (ref "J36") (pin "64") (pinfunction "64_64") (pintype "input+no_connect"))
    )
    (net (code "208") (name "unconnected-(J36-Pad65)") (class "Default")
      (node (ref "J36") (pin "65") (pinfunction "65_65") (pintype "input+no_connect"))
    )
    (net (code "209") (name "unconnected-(J36-Pad66)") (class "Default")
      (node (ref "J36") (pin "66") (pinfunction "66_66") (pintype "input+no_connect"))
    )
    (net (code "210") (name "unconnected-(J36-Pad67)") (class "Default")
      (node (ref "J36") (pin "67") (pinfunction "67_67") (pintype "input+no_connect"))
    )
    (net (code "211") (name "unconnected-(J36-Pad68)") (class "Default")
      (node (ref "J36") (pin "68") (pinfunction "68_68") (pintype "input+no_connect"))
    )
    (net (code "212") (name "unconnected-(J36-Pad71)") (class "Default")
      (node (ref "J36") (pin "71") (pinfunction "71_71") (pintype "input+no_connect"))
    )
    (net (code "213") (name "unconnected-(J36-Pad72)") (class "Default")
      (node (ref "J36") (pin "72") (pinfunction "72_72") (pintype "input+no_connect"))
    )
    (net (code "214") (name "unconnected-(J36-Pad73)") (class "Default")
      (node (ref "J36") (pin "73") (pinfunction "73_73") (pintype "input+no_connect"))
    )
    (net (code "215") (name "unconnected-(J36-Pad74)") (class "Default")
      (node (ref "J36") (pin "74") (pinfunction "74_74") (pintype "input+no_connect"))
    )
    (net (code "216") (name "unconnected-(J36-Pad75)") (class "Default")
      (node (ref "J36") (pin "75") (pinfunction "75_75") (pintype "input+no_connect"))
    )
    (net (code "217") (name "unconnected-(J36-Pad76)") (class "Default")
      (node (ref "J36") (pin "76") (pinfunction "76_76") (pintype "input+no_connect"))
    )
    (net (code "218") (name "unconnected-(J36-Pad81)") (class "Default")
      (node (ref "J36") (pin "81") (pinfunction "81_81") (pintype "input+no_connect"))
    )
    (net (code "219") (name "unconnected-(J36-Pad82)") (class "Default")
      (node (ref "J36") (pin "82") (pinfunction "82_82") (pintype "input+no_connect"))
    )
    (net (code "220") (name "unconnected-(J36-Pad83)") (class "Default")
      (node (ref "J36") (pin "83") (pinfunction "83_83") (pintype "input+no_connect"))
    )
    (net (code "221") (name "unconnected-(J36-Pad84)") (class "Default")
      (node (ref "J36") (pin "84") (pinfunction "84_84") (pintype "input+no_connect"))
    )
    (net (code "222") (name "unconnected-(J37-Pad1)") (class "Default")
      (node (ref "J37") (pin "1") (pinfunction "1_1") (pintype "input+no_connect"))
    )
    (net (code "223") (name "unconnected-(J37-Pad2)") (class "Default")
      (node (ref "J37") (pin "2") (pinfunction "2_2") (pintype "input+no_connect"))
    )
    (net (code "224") (name "unconnected-(J37-Pad3)") (class "Default")
      (node (ref "J37") (pin "3") (pinfunction "3_3") (pintype "input+no_connect"))
    )
    (net (code "225") (name "unconnected-(J37-Pad4)") (class "Default")
      (node (ref "J37") (pin "4") (pinfunction "4_4") (pintype "input+no_connect"))
    )
    (net (code "226") (name "unconnected-(J37-Pad5)") (class "Default")
      (node (ref "J37") (pin "5") (pinfunction "5_5") (pintype "input+no_connect"))
    )
    (net (code "227") (name "unconnected-(J37-Pad6)") (class "Default")
      (node (ref "J37") (pin "6") (pinfunction "6_6") (pintype "input+no_connect"))
    )
    (net (code "228") (name "unconnected-(J37-Pad7)") (class "Default")
      (node (ref "J37") (pin "7") (pinfunction "7_7") (pintype "input+no_connect"))
    )
    (net (code "229") (name "unconnected-(J37-Pad8)") (class "Default")
      (node (ref "J37") (pin "8") (pinfunction "8_8") (pintype "input+no_connect"))
    )
    (net (code "230") (name "unconnected-(J37-Pad11)") (class "Default")
      (node (ref "J37") (pin "11") (pinfunction "11_11") (pintype "input+no_connect"))
    )
    (net (code "231") (name "unconnected-(J37-Pad13)") (class "Default")
      (node (ref "J37") (pin "13") (pinfunction "13_13") (pintype "input+no_connect"))
    )
    (net (code "232") (name "unconnected-(J37-Pad16)") (class "Default")
      (node (ref "J37") (pin "16") (pinfunction "16_16") (pintype "input+no_connect"))
    )
    (net (code "233") (name "unconnected-(J37-Pad22)") (class "Default")
      (node (ref "J37") (pin "22") (pinfunction "22_22") (pintype "input+no_connect"))
    )
    (net (code "234") (name "unconnected-(J37-Pad28)") (class "Default")
      (node (ref "J37") (pin "28") (pinfunction "28_28") (pintype "input+no_connect"))
    )
    (net (code "235") (name "unconnected-(J37-Pad34)") (class "Default")
      (node (ref "J37") (pin "34") (pinfunction "34_34") (pintype "input+no_connect"))
    )
    (net (code "236") (name "unconnected-(J37-Pad41)") (class "Default")
      (node (ref "J37") (pin "41") (pinfunction "41_41") (pintype "input+no_connect"))
    )
    (net (code "237") (name "unconnected-(J37-Pad42)") (class "Default")
      (node (ref "J37") (pin "42") (pinfunction "42_42") (pintype "input+no_connect"))
    )
    (net (code "238") (name "unconnected-(J37-Pad43)") (class "Default")
      (node (ref "J37") (pin "43") (pinfunction "43_43") (pintype "input+no_connect"))
    )
    (net (code "239") (name "unconnected-(J37-Pad44)") (class "Default")
      (node (ref "J37") (pin "44") (pinfunction "44_44") (pintype "input+no_connect"))
    )
    (net (code "240") (name "unconnected-(J37-Pad45)") (class "Default")
      (node (ref "J37") (pin "45") (pinfunction "45_45") (pintype "input+no_connect"))
    )
    (net (code "241") (name "unconnected-(J37-Pad46)") (class "Default")
      (node (ref "J37") (pin "46") (pinfunction "46_46") (pintype "input+no_connect"))
    )
    (net (code "242") (name "unconnected-(J37-Pad47)") (class "Default")
      (node (ref "J37") (pin "47") (pinfunction "47_47") (pintype "input+no_connect"))
    )
    (net (code "243") (name "unconnected-(J37-Pad48)") (class "Default")
      (node (ref "J37") (pin "48") (pinfunction "48_48") (pintype "input+no_connect"))
    )
    (net (code "244") (name "unconnected-(J37-Pad51)") (class "Default")
      (node (ref "J37") (pin "51") (pinfunction "51_51") (pintype "input+no_connect"))
    )
    (net (code "245") (name "unconnected-(J37-Pad52)") (class "Default")
      (node (ref "J37") (pin "52") (pinfunction "52_52") (pintype "input+no_connect"))
    )
    (net (code "246") (name "unconnected-(J37-Pad53)") (class "Default")
      (node (ref "J37") (pin "53") (pinfunction "53_53") (pintype "input+no_connect"))
    )
    (net (code "247") (name "unconnected-(J37-Pad54)") (class "Default")
      (node (ref "J37") (pin "54") (pinfunction "54_54") (pintype "input+no_connect"))
    )
    (net (code "248") (name "unconnected-(J37-Pad55)") (class "Default")
      (node (ref "J37") (pin "55") (pinfunction "55_55") (pintype "input+no_connect"))
    )
    (net (code "249") (name "unconnected-(J37-Pad56)") (class "Default")
      (node (ref "J37") (pin "56") (pinfunction "56_56") (pintype "input+no_connect"))
    )
    (net (code "250") (name "unconnected-(J37-Pad57)") (class "Default")
      (node (ref "J37") (pin "57") (pinfunction "57_57") (pintype "input+no_connect"))
    )
    (net (code "251") (name "unconnected-(J37-Pad58)") (class "Default")
      (node (ref "J37") (pin "58") (pinfunction "58_58") (pintype "input+no_connect"))
    )
    (net (code "252") (name "unconnected-(J37-Pad61)") (class "Default")
      (node (ref "J37") (pin "61") (pinfunction "61_61") (pintype "input+no_connect"))
    )
    (net (code "253") (name "unconnected-(J37-Pad62)") (class "Default")
      (node (ref "J37") (pin "62") (pinfunction "62_62") (pintype "input+no_connect"))
    )
    (net (code "254") (name "unconnected-(J37-Pad63)") (class "Default")
      (node (ref "J37") (pin "63") (pinfunction "63_63") (pintype "input+no_connect"))
    )
    (net (code "255") (name "unconnected-(J37-Pad64)") (class "Default")
      (node (ref "J37") (pin "64") (pinfunction "64_64") (pintype "input+no_connect"))
    )
    (net (code "256") (name "unconnected-(J37-Pad65)") (class "Default")
      (node (ref "J37") (pin "65") (pinfunction "65_65") (pintype "input+no_connect"))
    )
    (net (code "257") (name "unconnected-(J37-Pad66)") (class "Default")
      (node (ref "J37") (pin "66") (pinfunction "66_66") (pintype "input+no_connect"))
    )
    (net (code "258") (name "unconnected-(J37-Pad67)") (class "Default")
      (node (ref "J37") (pin "67") (pinfunction "67_67") (pintype "input+no_connect"))
    )
    (net (code "259") (name "unconnected-(J37-Pad68)") (class "Default")
      (node (ref "J37") (pin "68") (pinfunction "68_68") (pintype "input+no_connect"))
    )
    (net (code "260") (name "unconnected-(J37-Pad71)") (class "Default")
      (node (ref "J37") (pin "71") (pinfunction "71_71") (pintype "input+no_connect"))
    )
    (net (code "261") (name "unconnected-(J37-Pad72)") (class "Default")
      (node (ref "J37") (pin "72") (pinfunction "72_72") (pintype "input+no_connect"))
    )
    (net (code "262") (name "unconnected-(J37-Pad73)") (class "Default")
      (node (ref "J37") (pin "73") (pinfunction "73_73") (pintype "input+no_connect"))
    )
    (net (code "263") (name "unconnected-(J37-Pad74)") (class "Default")
      (node (ref "J37") (pin "74") (pinfunction "74_74") (pintype "input+no_connect"))
    )
    (net (code "264") (name "unconnected-(J37-Pad75)") (class "Default")
      (node (ref "J37") (pin "75") (pinfunction "75_75") (pintype "input+no_connect"))
    )
    (net (code "265") (name "unconnected-(J37-Pad76)") (class "Default")
      (node (ref "J37") (pin "76") (pinfunction "76_76") (pintype "input+no_connect"))
    )
    (net (code "266") (name "unconnected-(J37-Pad77)") (class "Default")
      (node (ref "J37") (pin "77") (pinfunction "77_77") (pintype "input+no_connect"))
    )
    (net (code "267") (name "unconnected-(J37-Pad78)") (class "Default")
      (node (ref "J37") (pin "78") (pinfunction "78_78") (pintype "input+no_connect"))
    )
    (net (code "268") (name "unconnected-(J37-Pad79)") (class "Default")
      (node (ref "J37") (pin "79") (pinfunction "79_79") (pintype "input+no_connect"))
    )
    (net (code "269") (name "unconnected-(J37-Pad80)") (class "Default")
      (node (ref "J37") (pin "80") (pinfunction "80_80") (pintype "input+no_connect"))
    )
    (net (code "270") (name "unconnected-(J37-Pad81)") (class "Default")
      (node (ref "J37") (pin "81") (pinfunction "81_81") (pintype "input+no_connect"))
    )
    (net (code "271") (name "unconnected-(J37-Pad82)") (class "Default")
      (node (ref "J37") (pin "82") (pinfunction "82_82") (pintype "input+no_connect"))
    )
    (net (code "272") (name "unconnected-(J37-Pad83)") (class "Default")
      (node (ref "J37") (pin "83") (pinfunction "83_83") (pintype "input+no_connect"))
    )
    (net (code "273") (name "unconnected-(J37-Pad84)") (class "Default")
      (node (ref "J37") (pin "84") (pinfunction "84_84") (pintype "input+no_connect"))
    )
  )
)
